# LED_String_NE2G757GT.net
KiCad netlist of a schematic drawn in Altium Designer
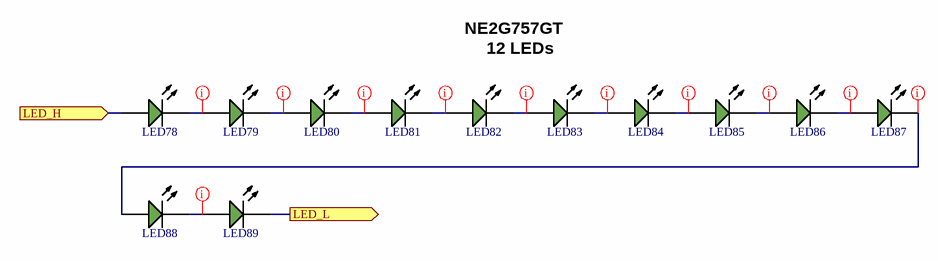
[diagram p0: LED_String_NE2G757GT.SchDoc]

(export (version "E")
  (design (tool "Eeschema 10.0.6"))
  (components
    (comp (ref "LED78")
      (value "NE2G757GT")
      (footprint "NE2G757GT")
      (description "SMD LED Green 3,5 V, 33 lm 3030 (1212)")
      (fields (field (name "MANUFACTURER") "Nichia"))
      (libsource (lib "ETHZ Vault") (part "LED Green"))
    )
    (comp (ref "LED79")
      (value "NE2G757GT")
      (footprint "NE2G757GT")
      (description "SMD LED Green 3,5 V, 33 lm 3030 (1212)")
      (fields (field (name "MANUFACTURER") "Nichia"))
      (libsource (lib "ETHZ Vault") (part "LED Green"))
    )
    (comp (ref "LED80")
      (value "NE2G757GT")
      (footprint "NE2G757GT")
      (description "SMD LED Green 3,5 V, 33 lm 3030 (1212)")
      (fields (field (name "MANUFACTURER") "Nichia"))
      (libsource (lib "ETHZ Vault") (part "LED Green"))
    )
    (comp (ref "LED81")
      (value "NE2G757GT")
      (footprint "NE2G757GT")
      (description "SMD LED Green 3,5 V, 33 lm 3030 (1212)")
      (fields (field (name "MANUFACTURER") "Nichia"))
      (libsource (lib "ETHZ Vault") (part "LED Green"))
    )
    (comp (ref "LED82")
      (value "NE2G757GT")
      (footprint "NE2G757GT")
      (description "SMD LED Green 3,5 V, 33 lm 3030 (1212)")
      (fields (field (name "MANUFACTURER") "Nichia"))
      (libsource (lib "ETHZ Vault") (part "LED Green"))
    )
    (comp (ref "LED83")
      (value "NE2G757GT")
      (footprint "NE2G757GT")
      (description "SMD LED Green 3,5 V, 33 lm 3030 (1212)")
      (fields (field (name "MANUFACTURER") "Nichia"))
      (libsource (lib "ETHZ Vault") (part "LED Green"))
    )
    (comp (ref "LED84")
      (value "NE2G757GT")
      (footprint "NE2G757GT")
      (description "SMD LED Green 3,5 V, 33 lm 3030 (1212)")
      (fields (field (name "MANUFACTURER") "Nichia"))
      (libsource (lib "ETHZ Vault") (part "LED Green"))
    )
    (comp (ref "LED85")
      (value "NE2G757GT")
      (footprint "NE2G757GT")
      (description "SMD LED Green 3,5 V, 33 lm 3030 (1212)")
      (fields (field (name "MANUFACTURER") "Nichia"))
      (libsource (lib "ETHZ Vault") (part "LED Green"))
    )
    (comp (ref "LED86")
      (value "NE2G757GT")
      (footprint "NE2G757GT")
      (description "SMD LED Green 3,5 V, 33 lm 3030 (1212)")
      (fields (field (name "MANUFACTURER") "Nichia"))
      (libsource (lib "ETHZ Vault") (part "LED Green"))
    )
    (comp (ref "LED87")
      (value "NE2G757GT")
      (footprint "NE2G757GT")
      (description "SMD LED Green 3,5 V, 33 lm 3030 (1212)")
      (fields (field (name "MANUFACTURER") "Nichia"))
      (libsource (lib "ETHZ Vault") (part "LED Green"))
    )
    (comp (ref "LED88")
      (value "NE2G757GT")
      (footprint "NE2G757GT")
      (description "SMD LED Green 3,5 V, 33 lm 3030 (1212)")
      (fields (field (name "MANUFACTURER") "Nichia"))
      (libsource (lib "ETHZ Vault") (part "LED Green"))
    )
    (comp (ref "LED89")
      (value "NE2G757GT")
      (footprint "NE2G757GT")
      (description "SMD LED Green 3,5 V, 33 lm 3030 (1212)")
      (fields (field (name "MANUFACTURER") "Nichia"))
      (libsource (lib "ETHZ Vault") (part "LED Green"))
    )
  )
  (nets
    (net (code "1") (name "/LED_H") (class "Default")
      (node (ref "LED78") (pin "2") (pinfunction "A_2") (pintype "passive"))
    )
    (net (code "2") (name "/LED_L") (class "Default")
      (node (ref "LED89") (pin "1") (pinfunction "K_1") (pintype "passive"))
    )
    (net (code "3") (name "Net-(LED78-K)") (class "Default")
      (node (ref "LED78") (pin "1") (pinfunction "K_1") (pintype "passive"))
      (node (ref "LED79") (pin "2") (pinfunction "A_2") (pintype "passive"))
    )
    (net (code "4") (name "Net-(LED79-K)") (class "Default")
      (node (ref "LED79") (pin "1") (pinfunction "K_1") (pintype "passive"))
      (node (ref "LED80") (pin "2") (pinfunction "A_2") (pintype "passive"))
    )
    (net (code "5") (name "Net-(LED80-K)") (class "Default")
      (node (ref "LED80") (pin "1") (pinfunction "K_1") (pintype "passive"))
      (node (ref "LED81") (pin "2") (pinfunction "A_2") (pintype "passive"))
    )
    (net (code "6") (name "Net-(LED81-K)") (class "Default")
      (node (ref "LED81") (pin "1") (pinfunction "K_1") (pintype "passive"))
      (node (ref "LED82") (pin "2") (pinfunction "A_2") (pintype "passive"))
    )
    (net (code "7") (name "Net-(LED82-K)") (class "Default")
      (node (ref "LED82") (pin "1") (pinfunction "K_1") (pintype "passive"))
      (node (ref "LED83") (pin "2") (pinfunction "A_2") (pintype "passive"))
    )
    (net (code "8") (name "Net-(LED83-K)") (class "Default")
      (node (ref "LED83") (pin "1") (pinfunction "K_1") (pintype "passive"))
      (node (ref "LED84") (pin "2") (pinfunction "A_2") (pintype "passive"))
    )
    (net (code "9") (name "Net-(LED84-K)") (class "Default")
      (node (ref "LED84") (pin "1") (pinfunction "K_1") (pintype "passive"))
      (node (ref "LED85") (pin "2") (pinfunction "A_2") (pintype "passive"))
    )
    (net (code "10") (name "Net-(LED85-K)") (class "Default")
      (node (ref "LED85") (pin "1") (pinfunction "K_1") (pintype "passive"))
      (node (ref "LED86") (pin "2") (pinfunction "A_2") (pintype "passive"))
    )
    (net (code "11") (name "Net-(LED86-K)") (class "Default")
      (node (ref "LED86") (pin "1") (pinfunction "K_1") (pintype "passive"))
      (node (ref "LED87") (pin "2") (pinfunction "A_2") (pintype "passive"))
    )
    (net (code "12") (name "Net-(LED87-K)") (class "Default")
      (node (ref "LED87") (pin "1") (pinfunction "K_1") (pintype "passive"))
      (node (ref "LED88") (pin "2") (pinfunction "A_2") (pintype "passive"))
    )
    (net (code "13") (name "Net-(LED88-K)") (class "Default")
      (node (ref "LED88") (pin "1") (pinfunction "K_1") (pintype "passive"))
      (node (ref "LED89") (pin "2") (pinfunction "A_2") (pintype "passive"))
    )
  )
)
